# DDR_Memory.net
KiCad netlist of a schematic drawn in Altium Designer
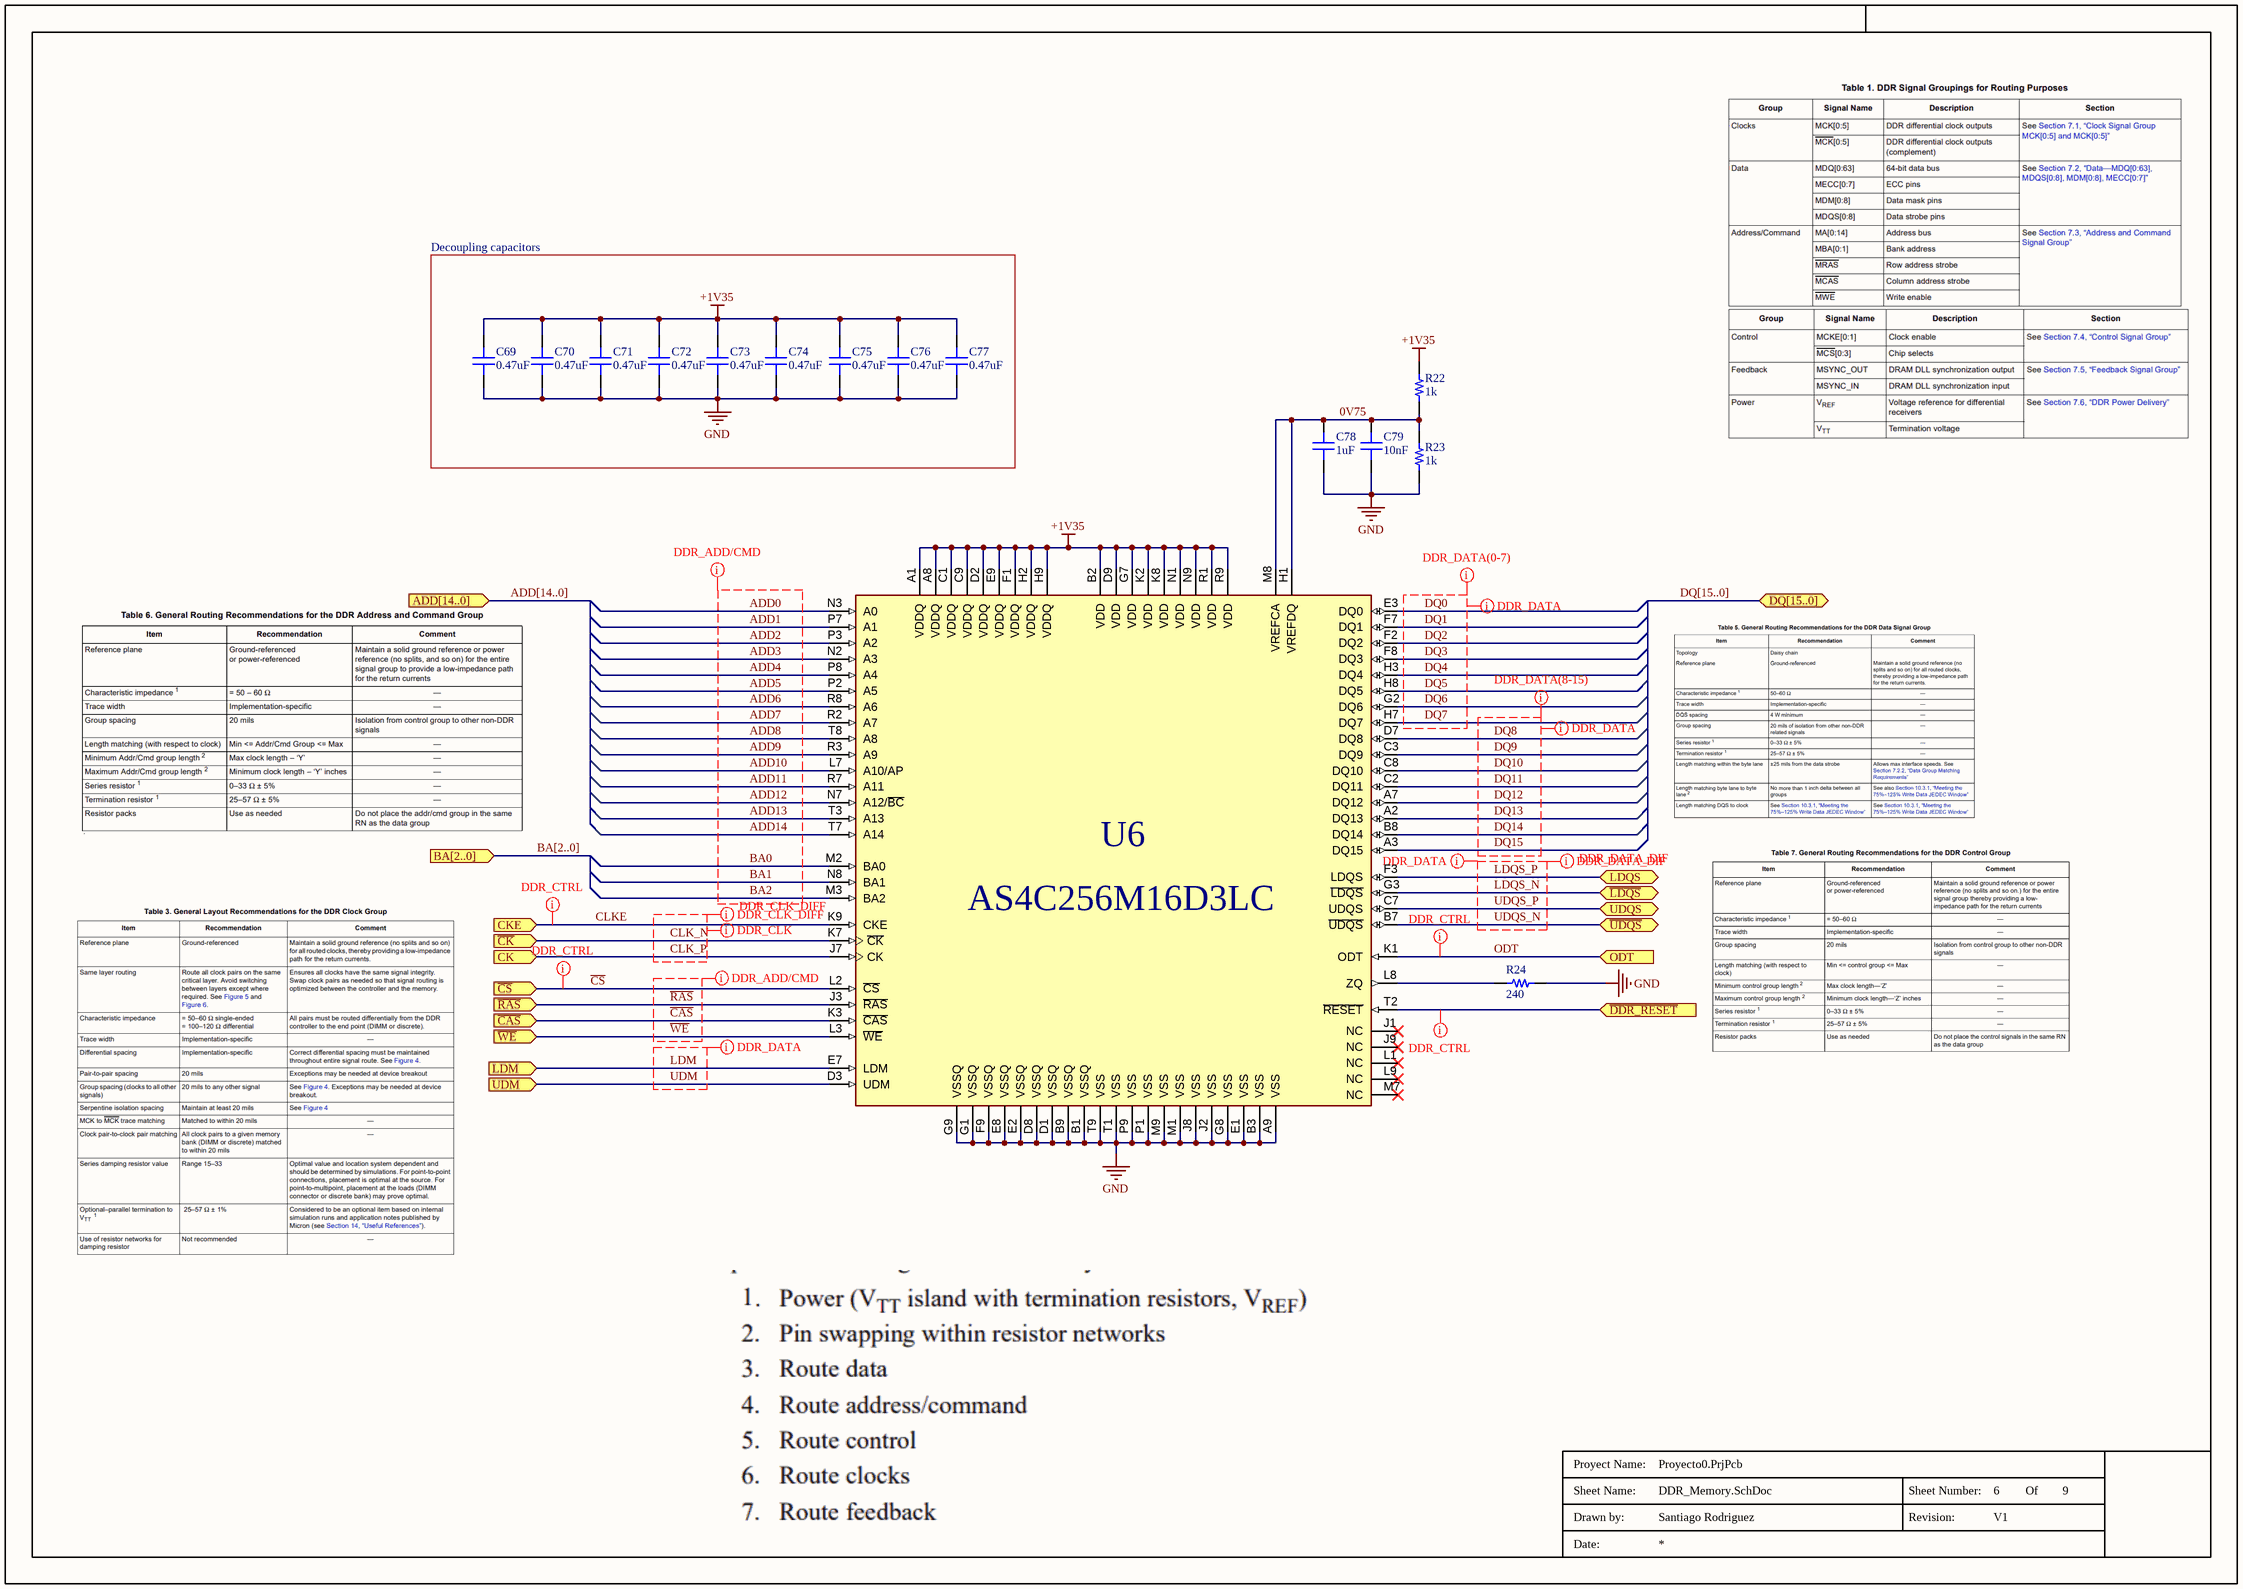
[diagram p0: DDR_Memory.SchDoc]

(export (version "E")
  (design (tool "Eeschema 10.0.6"))
  (components
    (comp (ref "C69")
      (value "0.47uF")
      (footprint "CAP0402")
      (description "CAP CER 0.47uF 10V X7R 0402 10%")
      (fields (field (name "PARTNUMBER") "C0603C474K4RAC") (field (name "TOLERANCE") "10%"))
      (libsource (lib "Pasivos") (part "C0402C474K8RAC"))
    )
    (comp (ref "C70")
      (value "0.47uF")
      (footprint "CAP0402")
      (description "CAP CER 0.47uF 10V X7R 0402 10%")
      (fields (field (name "PARTNUMBER") "C0603C474K4RAC") (field (name "TOLERANCE") "10%"))
      (libsource (lib "Pasivos") (part "C0402C474K8RAC"))
    )
    (comp (ref "C71")
      (value "0.47uF")
      (footprint "CAP0402")
      (description "CAP CER 0.47uF 10V X7R 0402 10%")
      (fields (field (name "PARTNUMBER") "C0603C474K4RAC") (field (name "TOLERANCE") "10%"))
      (libsource (lib "Pasivos") (part "C0402C474K8RAC"))
    )
    (comp (ref "C72")
      (value "0.47uF")
      (footprint "CAP0402")
      (description "CAP CER 0.47uF 10V X7R 0402 10%")
      (fields (field (name "PARTNUMBER") "C0603C474K4RAC") (field (name "TOLERANCE") "10%"))
      (libsource (lib "Pasivos") (part "C0402C474K8RAC"))
    )
    (comp (ref "C73")
      (value "0.47uF")
      (footprint "CAP0402")
      (description "CAP CER 0.47uF 10V X7R 0402 10%")
      (fields (field (name "PARTNUMBER") "C0603C474K4RAC") (field (name "TOLERANCE") "10%"))
      (libsource (lib "Pasivos") (part "C0402C474K8RAC"))
    )
    (comp (ref "C74")
      (value "0.47uF")
      (footprint "CAP0402")
      (description "CAP CER 0.47uF 10V X7R 0402 10%")
      (fields (field (name "PARTNUMBER") "C0603C474K4RAC") (field (name "TOLERANCE") "10%"))
      (libsource (lib "Pasivos") (part "C0402C474K8RAC"))
    )
    (comp (ref "C75")
      (value "0.47uF")
      (footprint "CAP0402")
      (description "CAP CER 0.47uF 10V X7R 0402 10%")
      (fields (field (name "PARTNUMBER") "C0603C474K4RAC") (field (name "TOLERANCE") "10%"))
      (libsource (lib "Pasivos") (part "C0402C474K8RAC"))
    )
    (comp (ref "C76")
      (value "0.47uF")
      (footprint "CAP0402")
      (description "CAP CER 0.47uF 10V X7R 0402 10%")
      (fields (field (name "PARTNUMBER") "C0603C474K4RAC") (field (name "TOLERANCE") "10%"))
      (libsource (lib "Pasivos") (part "C0402C474K8RAC"))
    )
    (comp (ref "C77")
      (value "0.47uF")
      (footprint "CAP0402")
      (description "CAP CER 0.47uF 10V X7R 0402 10%")
      (fields (field (name "PARTNUMBER") "C0603C474K4RAC") (field (name "TOLERANCE") "10%"))
      (libsource (lib "Pasivos") (part "C0402C474K8RAC"))
    )
    (comp (ref "C78")
      (value "1uF")
      (footprint "CAP0402")
      (description "CAP CER 1uF 16V X7R 0402 10%")
      (fields (field (name "TOLERANCE") "10%") (field (name "MANUFACTURER") "Kemet"))
      (libsource (lib "Pasivos") (part "C0402C105K4RAC"))
    )
    (comp (ref "C79")
      (value "10nF")
      (footprint "CAP0402")
      (description "CAP CER 10nF 16V X7R 0402 10%")
      (fields (field (name "TOLERANCE") "10%") (field (name "VOLTAGE") "16V"))
      (libsource (lib "Pasivos") (part "C0402C103K4RAC"))
    )
    (comp (ref "R22")
      (value "1k")
      (footprint "RES0402")
      (description "RES SMD 1K OHM 1% 0.063W 0402")
      (fields (field (name "TOLERANCE") "1%") (field (name "MANUFACTURER") "Vishay"))
      (libsource (lib "Pasivos") (part "CRCW04021K00FK"))
    )
    (comp (ref "R23")
      (value "1k")
      (footprint "RES0402")
      (description "RES SMD 1K OHM 1% 0.063W 0402")
      (fields (field (name "TOLERANCE") "1%") (field (name "MANUFACTURER") "Vishay"))
      (libsource (lib "Pasivos") (part "CRCW04021K00FK"))
    )
    (comp (ref "R24")
      (value "240")
      (footprint "RES0402")
      (description "RES SMD 240 OHM 1% 1/10W 0402")
      (fields (field (name "MANUFACTURER") "Vishay") (field (name "TOLERANCE") "1%"))
      (libsource (lib "Pasivos") (part "CRCW0402240RFK"))
    )
    (comp (ref "U6")
      (value "AS4C256M16D3LC")
      (footprint "FBGA-96")
      (description "256M x 16 bit DDR3L Synchronous DRAM (SDRAM)")
      (libsource (lib "Integrated_Circuits") (part "DDR3 AS4C256M16D3LC"))
    )
  )
  (nets
    (net (code "1") (name "+1V35") (class "Default")
      (node (ref "C69") (pin "2") (pinfunction "2_2") (pintype "passive"))
      (node (ref "C70") (pin "2") (pinfunction "2_2") (pintype "passive"))
      (node (ref "C71") (pin "2") (pinfunction "2_2") (pintype "passive"))
      (node (ref "C72") (pin "2") (pinfunction "2_2") (pintype "passive"))
      (node (ref "C73") (pin "2") (pinfunction "2_2") (pintype "passive"))
      (node (ref "C74") (pin "2") (pinfunction "2_2") (pintype "passive"))
      (node (ref "C75") (pin "2") (pinfunction "2_2") (pintype "passive"))
      (node (ref "C76") (pin "2") (pinfunction "2_2") (pintype "passive"))
      (node (ref "C77") (pin "2") (pinfunction "2_2") (pintype "passive"))
      (node (ref "R22") (pin "2") (pinfunction "2_2") (pintype "passive"))
      (node (ref "U6") (pin "A1") (pinfunction "VDDQ_A1") (pintype "power_in"))
      (node (ref "U6") (pin "A8") (pinfunction "VDDQ_A8") (pintype "power_in"))
      (node (ref "U6") (pin "B2") (pinfunction "VDD_B2") (pintype "power_in"))
      (node (ref "U6") (pin "C1") (pinfunction "VDDQ_C1") (pintype "power_in"))
      (node (ref "U6") (pin "C9") (pinfunction "VDDQ_C9") (pintype "power_in"))
      (node (ref "U6") (pin "D2") (pinfunction "VDDQ_D2") (pintype "power_in"))
      (node (ref "U6") (pin "D9") (pinfunction "VDD_D9") (pintype "power_in"))
      (node (ref "U6") (pin "E9") (pinfunction "VDDQ_E9") (pintype "power_in"))
      (node (ref "U6") (pin "F1") (pinfunction "VDDQ_F1") (pintype "power_in"))
      (node (ref "U6") (pin "G7") (pinfunction "VDD_G7") (pintype "power_in"))
      (node (ref "U6") (pin "H2") (pinfunction "VDDQ_H2") (pintype "power_in"))
      (node (ref "U6") (pin "H9") (pinfunction "VDDQ_H9") (pintype "power_in"))
      (node (ref "U6") (pin "K2") (pinfunction "VDD_K2") (pintype "power_in"))
      (node (ref "U6") (pin "K8") (pinfunction "VDD_K8") (pintype "power_in"))
      (node (ref "U6") (pin "N1") (pinfunction "VDD_N1") (pintype "power_in"))
      (node (ref "U6") (pin "N9") (pinfunction "VDD_N9") (pintype "power_in"))
      (node (ref "U6") (pin "R1") (pinfunction "VDD_R1") (pintype "power_in"))
      (node (ref "U6") (pin "R9") (pinfunction "VDD_R9") (pintype "power_in"))
    )
    (net (code "2") (name "/0V75") (class "Default")
      (node (ref "C78") (pin "2") (pinfunction "2_2") (pintype "passive"))
      (node (ref "C79") (pin "2") (pinfunction "2_2") (pintype "passive"))
      (node (ref "R22") (pin "1") (pinfunction "1_1") (pintype "passive"))
      (node (ref "R23") (pin "2") (pinfunction "2_2") (pintype "passive"))
      (node (ref "U6") (pin "H1") (pinfunction "VREFDQ_H1") (pintype "power_in"))
      (node (ref "U6") (pin "M8") (pinfunction "VREFCA_M8") (pintype "power_in"))
    )
    (net (code "3") (name "/ADD0") (class "Default")
      (node (ref "U6") (pin "N3") (pinfunction "A0_N3") (pintype "input"))
    )
    (net (code "4") (name "/ADD1") (class "Default")
      (node (ref "U6") (pin "P7") (pinfunction "A1_P7") (pintype "input"))
    )
    (net (code "5") (name "/ADD2") (class "Default")
      (node (ref "U6") (pin "P3") (pinfunction "A2_P3") (pintype "input"))
    )
    (net (code "6") (name "/ADD3") (class "Default")
      (node (ref "U6") (pin "N2") (pinfunction "A3_N2") (pintype "input"))
    )
    (net (code "7") (name "/ADD4") (class "Default")
      (node (ref "U6") (pin "P8") (pinfunction "A4_P8") (pintype "input"))
    )
    (net (code "8") (name "/ADD5") (class "Default")
      (node (ref "U6") (pin "P2") (pinfunction "A5_P2") (pintype "input"))
    )
    (net (code "9") (name "/ADD6") (class "Default")
      (node (ref "U6") (pin "R8") (pinfunction "A6_R8") (pintype "input"))
    )
    (net (code "10") (name "/ADD7") (class "Default")
      (node (ref "U6") (pin "R2") (pinfunction "A7_R2") (pintype "input"))
    )
    (net (code "11") (name "/ADD8") (class "Default")
      (node (ref "U6") (pin "T8") (pinfunction "A8_T8") (pintype "input"))
    )
    (net (code "12") (name "/ADD9") (class "Default")
      (node (ref "U6") (pin "R3") (pinfunction "A9_R3") (pintype "input"))
    )
    (net (code "13") (name "/ADD10") (class "Default")
      (node (ref "U6") (pin "L7") (pinfunction "A10/AP_L7") (pintype "input"))
    )
    (net (code "14") (name "/ADD11") (class "Default")
      (node (ref "U6") (pin "R7") (pinfunction "A11_R7") (pintype "input"))
    )
    (net (code "15") (name "/ADD12") (class "Default")
      (node (ref "U6") (pin "N7") (pinfunction "A12/~{BC}_N7") (pintype "input"))
    )
    (net (code "16") (name "/ADD13") (class "Default")
      (node (ref "U6") (pin "T3") (pinfunction "A13_T3") (pintype "input"))
    )
    (net (code "17") (name "/ADD14") (class "Default")
      (node (ref "U6") (pin "T7") (pinfunction "A14_T7") (pintype "input"))
    )
    (net (code "19") (name "/BA0") (class "Default")
      (node (ref "U6") (pin "M2") (pinfunction "BA0_M2") (pintype "input"))
    )
    (net (code "20") (name "/BA1") (class "Default")
      (node (ref "U6") (pin "N8") (pinfunction "BA1_N8") (pintype "input"))
    )
    (net (code "21") (name "/BA2") (class "Default")
      (node (ref "U6") (pin "M3") (pinfunction "BA2_M3") (pintype "input"))
    )
    (net (code "23") (name "/CLKE") (class "Default")
      (node (ref "U6") (pin "K9") (pinfunction "CKE_K9") (pintype "input"))
    )
    (net (code "24") (name "/CLK_N") (class "Default")
      (node (ref "U6") (pin "K7") (pinfunction "~{CK}_K7") (pintype "input"))
    )
    (net (code "25") (name "/CLK_P") (class "Default")
      (node (ref "U6") (pin "J7") (pinfunction "CK_J7") (pintype "input"))
    )
    (net (code "26") (name "/DQ0") (class "Default")
      (node (ref "U6") (pin "E3") (pinfunction "DQ0_E3") (pintype "bidirectional"))
    )
    (net (code "27") (name "/DQ1") (class "Default")
      (node (ref "U6") (pin "F7") (pinfunction "DQ1_F7") (pintype "bidirectional"))
    )
    (net (code "28") (name "/DQ2") (class "Default")
      (node (ref "U6") (pin "F2") (pinfunction "DQ2_F2") (pintype "bidirectional"))
    )
    (net (code "29") (name "/DQ3") (class "Default")
      (node (ref "U6") (pin "F8") (pinfunction "DQ3_F8") (pintype "bidirectional"))
    )
    (net (code "30") (name "/DQ4") (class "Default")
      (node (ref "U6") (pin "H3") (pinfunction "DQ4_H3") (pintype "bidirectional"))
    )
    (net (code "31") (name "/DQ5") (class "Default")
      (node (ref "U6") (pin "H8") (pinfunction "DQ5_H8") (pintype "bidirectional"))
    )
    (net (code "32") (name "/DQ6") (class "Default")
      (node (ref "U6") (pin "G2") (pinfunction "DQ6_G2") (pintype "bidirectional"))
    )
    (net (code "33") (name "/DQ7") (class "Default")
      (node (ref "U6") (pin "H7") (pinfunction "DQ7_H7") (pintype "bidirectional"))
    )
    (net (code "34") (name "/DQ8") (class "Default")
      (node (ref "U6") (pin "D7") (pinfunction "DQ8_D7") (pintype "bidirectional"))
    )
    (net (code "35") (name "/DQ9") (class "Default")
      (node (ref "U6") (pin "C3") (pinfunction "DQ9_C3") (pintype "bidirectional"))
    )
    (net (code "36") (name "/DQ10") (class "Default")
      (node (ref "U6") (pin "C8") (pinfunction "DQ10_C8") (pintype "bidirectional"))
    )
    (net (code "37") (name "/DQ11") (class "Default")
      (node (ref "U6") (pin "C2") (pinfunction "DQ11_C2") (pintype "bidirectional"))
    )
    (net (code "38") (name "/DQ12") (class "Default")
      (node (ref "U6") (pin "A7") (pinfunction "DQ12_A7") (pintype "bidirectional"))
    )
    (net (code "39") (name "/DQ13") (class "Default")
      (node (ref "U6") (pin "A2") (pinfunction "DQ13_A2") (pintype "bidirectional"))
    )
    (net (code "40") (name "/DQ14") (class "Default")
      (node (ref "U6") (pin "B8") (pinfunction "DQ14_B8") (pintype "bidirectional"))
    )
    (net (code "41") (name "/DQ15") (class "Default")
      (node (ref "U6") (pin "A3") (pinfunction "DQ15_A3") (pintype "bidirectional"))
    )
    (net (code "43") (name "/LDM") (class "Default")
      (node (ref "U6") (pin "E7") (pinfunction "LDM_E7") (pintype "input"))
    )
    (net (code "44") (name "/LDQS_N") (class "Default")
      (node (ref "U6") (pin "G3") (pinfunction "~{LDQS}_G3") (pintype "bidirectional"))
    )
    (net (code "45") (name "/LDQS_P") (class "Default")
      (node (ref "U6") (pin "F3") (pinfunction "LDQS_F3") (pintype "bidirectional"))
    )
    (net (code "46") (name "/ODT") (class "Default")
      (node (ref "U6") (pin "K1") (pinfunction "ODT_K1") (pintype "input"))
    )
    (net (code "47") (name "/UDM") (class "Default")
      (node (ref "U6") (pin "D3") (pinfunction "UDM_D3") (pintype "input"))
    )
    (net (code "48") (name "/UDQS_N") (class "Default")
      (node (ref "U6") (pin "B7") (pinfunction "~{UDQS}_B7") (pintype "bidirectional"))
    )
    (net (code "49") (name "/UDQS_P") (class "Default")
      (node (ref "U6") (pin "C7") (pinfunction "UDQS_C7") (pintype "bidirectional"))
    )
    (net (code "50") (name "/~{CAS}") (class "Default")
      (node (ref "U6") (pin "K3") (pinfunction "~{CAS}_K3") (pintype "input"))
    )
    (net (code "51") (name "/~{CS}") (class "Default")
      (node (ref "U6") (pin "L2") (pinfunction "~{CS}_L2") (pintype "input"))
    )
    (net (code "52") (name "/~{DDR_RESET}") (class "Default")
      (node (ref "U6") (pin "T2") (pinfunction "~{RESET}_T2") (pintype "input"))
    )
    (net (code "53") (name "/~{RAS}") (class "Default")
      (node (ref "U6") (pin "J3") (pinfunction "~{RAS}_J3") (pintype "input"))
    )
    (net (code "54") (name "/~{WE}") (class "Default")
      (node (ref "U6") (pin "L3") (pinfunction "~{WE}_L3") (pintype "input"))
    )
    (net (code "55") (name "GND") (class "Default")
      (node (ref "C69") (pin "1") (pinfunction "1_1") (pintype "passive"))
      (node (ref "C70") (pin "1") (pinfunction "1_1") (pintype "passive"))
      (node (ref "C71") (pin "1") (pinfunction "1_1") (pintype "passive"))
      (node (ref "C72") (pin "1") (pinfunction "1_1") (pintype "passive"))
      (node (ref "C73") (pin "1") (pinfunction "1_1") (pintype "passive"))
      (node (ref "C74") (pin "1") (pinfunction "1_1") (pintype "passive"))
      (node (ref "C75") (pin "1") (pinfunction "1_1") (pintype "passive"))
      (node (ref "C76") (pin "1") (pinfunction "1_1") (pintype "passive"))
      (node (ref "C77") (pin "1") (pinfunction "1_1") (pintype "passive"))
      (node (ref "C78") (pin "1") (pinfunction "1_1") (pintype "passive"))
      (node (ref "C79") (pin "1") (pinfunction "1_1") (pintype "passive"))
      (node (ref "R23") (pin "1") (pinfunction "1_1") (pintype "passive"))
      (node (ref "R24") (pin "2") (pinfunction "2_2") (pintype "passive"))
      (node (ref "U6") (pin "A9") (pinfunction "VSS_A9") (pintype "power_in"))
      (node (ref "U6") (pin "B1") (pinfunction "VSSQ_B1") (pintype "power_in"))
      (node (ref "U6") (pin "B3") (pinfunction "VSS_B3") (pintype "power_in"))
      (node (ref "U6") (pin "B9") (pinfunction "VSSQ_B9") (pintype "power_in"))
      (node (ref "U6") (pin "D1") (pinfunction "VSSQ_D1") (pintype "power_in"))
      (node (ref "U6") (pin "D8") (pinfunction "VSSQ_D8") (pintype "power_in"))
      (node (ref "U6") (pin "E1") (pinfunction "VSS_E1") (pintype "power_in"))
      (node (ref "U6") (pin "E2") (pinfunction "VSSQ_E2") (pintype "power_in"))
      (node (ref "U6") (pin "E8") (pinfunction "VSSQ_E8") (pintype "power_in"))
      (node (ref "U6") (pin "F9") (pinfunction "VSSQ_F9") (pintype "power_in"))
      (node (ref "U6") (pin "G1") (pinfunction "VSSQ_G1") (pintype "power_in"))
      (node (ref "U6") (pin "G8") (pinfunction "VSS_G8") (pintype "power_in"))
      (node (ref "U6") (pin "G9") (pinfunction "VSSQ_G9") (pintype "power_in"))
      (node (ref "U6") (pin "J2") (pinfunction "VSS_J2") (pintype "power_in"))
      (node (ref "U6") (pin "J8") (pinfunction "VSS_J8") (pintype "power_in"))
      (node (ref "U6") (pin "M1") (pinfunction "VSS_M1") (pintype "power_in"))
      (node (ref "U6") (pin "M9") (pinfunction "VSS_M9") (pintype "power_in"))
      (node (ref "U6") (pin "P1") (pinfunction "VSS_P1") (pintype "power_in"))
      (node (ref "U6") (pin "P9") (pinfunction "VSS_P9") (pintype "power_in"))
      (node (ref "U6") (pin "T1") (pinfunction "VSS_T1") (pintype "power_in"))
      (node (ref "U6") (pin "T9") (pinfunction "VSS_T9") (pintype "power_in"))
    )
    (net (code "56") (name "Net-(U6-ZQ)") (class "Default")
      (node (ref "R24") (pin "1") (pinfunction "1_1") (pintype "passive"))
      (node (ref "U6") (pin "L8") (pinfunction "ZQ_L8") (pintype "output"))
    )
    (net (code "57") (name "unconnected-(U6-NC-PadJ1)") (class "Default")
      (node (ref "U6") (pin "J1") (pinfunction "NC_J1") (pintype "passive+no_connect"))
    )
    (net (code "58") (name "unconnected-(U6-NC-PadJ9)") (class "Default")
      (node (ref "U6") (pin "J9") (pinfunction "NC_J9") (pintype "passive+no_connect"))
    )
    (net (code "59") (name "unconnected-(U6-NC-PadL1)") (class "Default")
      (node (ref "U6") (pin "L1") (pinfunction "NC_L1") (pintype "passive+no_connect"))
    )
    (net (code "60") (name "unconnected-(U6-NC-PadL9)") (class "Default")
      (node (ref "U6") (pin "L9") (pinfunction "NC_L9") (pintype "passive+no_connect"))
    )
    (net (code "61") (name "unconnected-(U6-NC-PadM7)") (class "Default")
      (node (ref "U6") (pin "M7") (pinfunction "NC_M7") (pintype "passive+no_connect"))
    )
  )
)
